# RTCE.net
KiCad netlist of a schematic drawn in Altium Designer
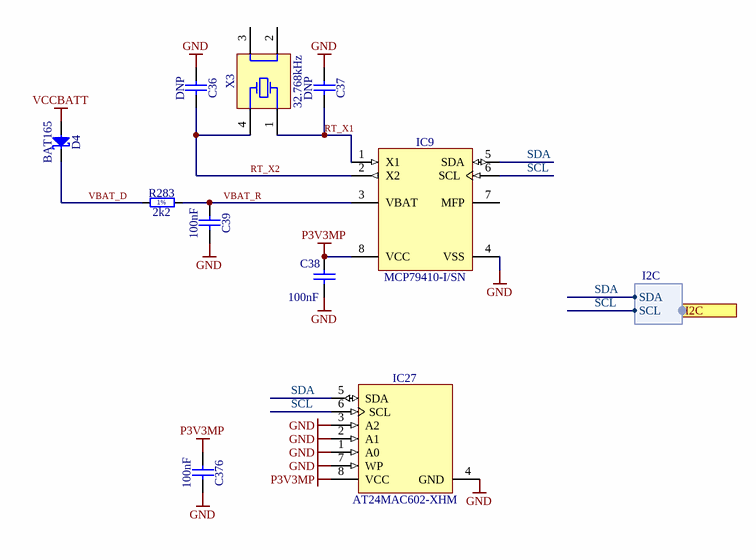
[diagram p0: RTCE.SchDoc]

(export (version "E")
  (design (tool "Eeschema 10.0.6"))
  (components
    (comp (ref "C36")
      (value "DNP")
      (footprint "CAPC1005X55N")
      (description "Non-polarised capacitor")
      (fields
        (field (name "PART NUMBER") "CC0402_15PF_50V_5%_NP0")
        (field (name "VOLTAGE") "50V")
        (field (name "AUTHOR") "CERN DEM JLC")
      )
      (libsource (lib "Capacitors") (part "Capacitor - non polarized"))
    )
    (comp (ref "C37")
      (value "DNP")
      (footprint "CAPC1005X55N")
      (description "Non-polarised capacitor")
      (fields
        (field (name "PART NUMBER") "CC0402_15PF_50V_5%_NP0")
        (field (name "VOLTAGE") "50V")
        (field (name "AUTHOR") "CERN DEM JLC")
      )
      (libsource (lib "Capacitors") (part "Capacitor - non polarized"))
    )
    (comp (ref "C38")
      (value "100nF")
      (footprint "CAPC0603X33N")
      (description "Non-polarised capacitor")
      (fields
        (field (name "PART NUMBER") "CC0201_100NF_6.3V_10%_X5R")
        (field (name "VOLTAGE") "6.3V")
        (field (name "AUTHOR") "CERN DEM JLC")
      )
      (libsource (lib "Capacitors") (part "Capacitor - non polarized"))
    )
    (comp (ref "C39")
      (value "100nF")
      (footprint "CAPC0603X33N")
      (description "Non-polarised capacitor")
      (fields
        (field (name "PART NUMBER") "CC0201_100NF_6.3V_10%_X5R")
        (field (name "VOLTAGE") "6.3V")
        (field (name "AUTHOR") "CERN DEM JLC")
      )
      (libsource (lib "Capacitors") (part "Capacitor - non polarized"))
    )
    (comp (ref "C376")
      (value "100nF")
      (footprint "CAPC0603X33N")
      (description "Non-polarised capacitor")
      (fields
        (field (name "PART NUMBER") "CC0201_100NF_6.3V_10%_X5R")
        (field (name "VOLTAGE") "6.3V")
        (field (name "AUTHOR") "CERN DEM JLC")
      )
      (libsource (lib "Capacitors") (part "Capacitor - non polarized"))
    )
    (comp (ref "D4")
      (value "BAT165")
      (footprint "SOD2512X110N")
      (description "Schottky Diode")
      (fields
        (field (name "VOLTAGE") "40V")
        (field (name "POWER") "750mA")
        (field (name "AUTHOR") "CERN DEM JLC")
      )
      (libsource (lib "ICs And Semiconductors") (part "Diode Schottky"))
    )
    (comp (ref "IC9")
      (value "MCP79410-I/SN")
      (footprint "SOIC127P600X175-8N")
      (description "I2C Real-Time Clock/Calendar with EEPROM, SRAM, Unique ID and Battery Switchover")
      (fields (field (name "MANUFACTURER") "MICROCHIP TECHNOLOGY") (field (name "AUTHOR") "CERN DEM JMW"))
      (libsource (lib "ICs And Semiconductors") (part "MCP79410"))
    )
    (comp (ref "IC27")
      (value "AT24MAC602-XHM")
      (footprint "SOP65P640X120-8N")
      (description "1.7V to 5.5V, I2C-Compatible (2-wire) 2-Kbit (256 x 8) Serial EEPROM")
      (fields (field (name "MANUFACTURER") "ATMEL") (field (name "AUTHOR") "CERN DEM MR"))
      (libsource (lib "ICs And Semiconductors") (part "AT24MAC602-XHM"))
    )
    (comp (ref "R283")
      (value "2k2")
      (footprint "RESC1005X40N")
      (description "Resistor - 1%")
      (fields
        (field (name "PART NUMBER") "R0402_2K2_1%_0.0625W_100PPM")
        (field (name "POWER") "0.0625W")
        (field (name "AUTHOR") "CERN DEM JLC")
      )
      (libsource (lib "Resistors") (part "Resistor - 1%"))
    )
    (comp (ref "X3")
      (value "32.768kHz")
      (footprint "XTAL_ABRACON_ABS25")
      (description "Crystal 4 pins 1=XTAL Control 2 And 3=NC 4=XTAL")
      (fields
        (field (name "PART NUMBER") "XTAL_32.768KHZ_ABRACON_ABS25-32.768KHZ-T")
        (field (name "MANUFACTURER") "ABRACON")
        (field (name "AUTHOR") "CERN DEM JMW")
      )
      (libsource (lib "ICs And Semiconductors") (part "Quartz Crystal 1X 2-3NC 4X"))
    )
  )
  (nets
    (net (code "2") (name "/RT_X1") (class "Default")
      (node (ref "C37") (pin "2") (pinfunction "2_2") (pintype "passive"))
      (node (ref "IC9") (pin "1") (pinfunction "X1_1") (pintype "input"))
      (node (ref "X3") (pin "1") (pinfunction "X_1") (pintype "passive"))
    )
    (net (code "3") (name "/RT_X2") (class "Default")
      (node (ref "C36") (pin "2") (pinfunction "2_2") (pintype "passive"))
      (node (ref "IC9") (pin "2") (pinfunction "X2_2") (pintype "output"))
      (node (ref "X3") (pin "4") (pinfunction "X_4") (pintype "passive"))
    )
    (net (code "4") (name "/SCL") (class "Default")
      (node (ref "IC27") (pin "6") (pinfunction "SCL_6") (pintype "input"))
      (node (ref "IC9") (pin "6") (pinfunction "SCL_6") (pintype "input"))
    )
    (net (code "5") (name "/SDA") (class "Default")
      (node (ref "IC27") (pin "5") (pinfunction "SDA_5") (pintype "bidirectional"))
      (node (ref "IC9") (pin "5") (pinfunction "SDA_5") (pintype "bidirectional"))
    )
    (net (code "6") (name "/VBAT_D") (class "Default")
      (node (ref "D4") (pin "1") (pinfunction "C_1") (pintype "passive"))
      (node (ref "R283") (pin "1") (pinfunction "1_1") (pintype "passive"))
    )
    (net (code "7") (name "/VBAT_R") (class "Default")
      (node (ref "C39") (pin "1") (pinfunction "1_1") (pintype "passive"))
      (node (ref "IC9") (pin "3") (pinfunction "VBAT_3") (pintype "power_in"))
      (node (ref "R283") (pin "2") (pinfunction "2_2") (pintype "passive"))
    )
    (net (code "9") (name "GND") (class "Default")
      (node (ref "C36") (pin "1") (pinfunction "1_1") (pintype "passive"))
      (node (ref "C37") (pin "1") (pinfunction "1_1") (pintype "passive"))
      (node (ref "C376") (pin "2") (pinfunction "2_2") (pintype "passive"))
      (node (ref "C38") (pin "2") (pinfunction "2_2") (pintype "passive"))
      (node (ref "C39") (pin "2") (pinfunction "2_2") (pintype "passive"))
      (node (ref "IC27") (pin "1") (pinfunction "A0_1") (pintype "input"))
      (node (ref "IC27") (pin "2") (pinfunction "A1_2") (pintype "input"))
      (node (ref "IC27") (pin "3") (pinfunction "A2_3") (pintype "input"))
      (node (ref "IC27") (pin "4") (pinfunction "GND_4") (pintype "power_in"))
      (node (ref "IC27") (pin "7") (pinfunction "WP_7") (pintype "input"))
      (node (ref "IC9") (pin "4") (pinfunction "VSS_4") (pintype "power_in"))
    )
    (net (code "10") (name "P3V3MP") (class "Default")
      (node (ref "C376") (pin "1") (pinfunction "1_1") (pintype "passive"))
      (node (ref "C38") (pin "1") (pinfunction "1_1") (pintype "passive"))
      (node (ref "IC27") (pin "8") (pinfunction "VCC_8") (pintype "power_in"))
      (node (ref "IC9") (pin "8") (pinfunction "VCC_8") (pintype "power_in"))
    )
    (net (code "11") (name "VCCBATT") (class "Default")
      (node (ref "D4") (pin "2") (pinfunction "A_2") (pintype "passive"))
    )
    (net (code "12") (name "unconnected-(IC9-MFP-Pad7)") (class "Default")
      (node (ref "IC9") (pin "7") (pinfunction "MFP_7") (pintype "open_collector"))
    )
    (net (code "13") (name "unconnected-(X3-GND-Pad2)") (class "Default")
      (node (ref "X3") (pin "2") (pinfunction "GND_2") (pintype "power_in"))
    )
    (net (code "14") (name "unconnected-(X3-GND-Pad3)") (class "Default")
      (node (ref "X3") (pin "3") (pinfunction "GND_3") (pintype "power_in"))
    )
  )
)
